# Power.net
KiCad netlist of a schematic drawn in Altium Designer
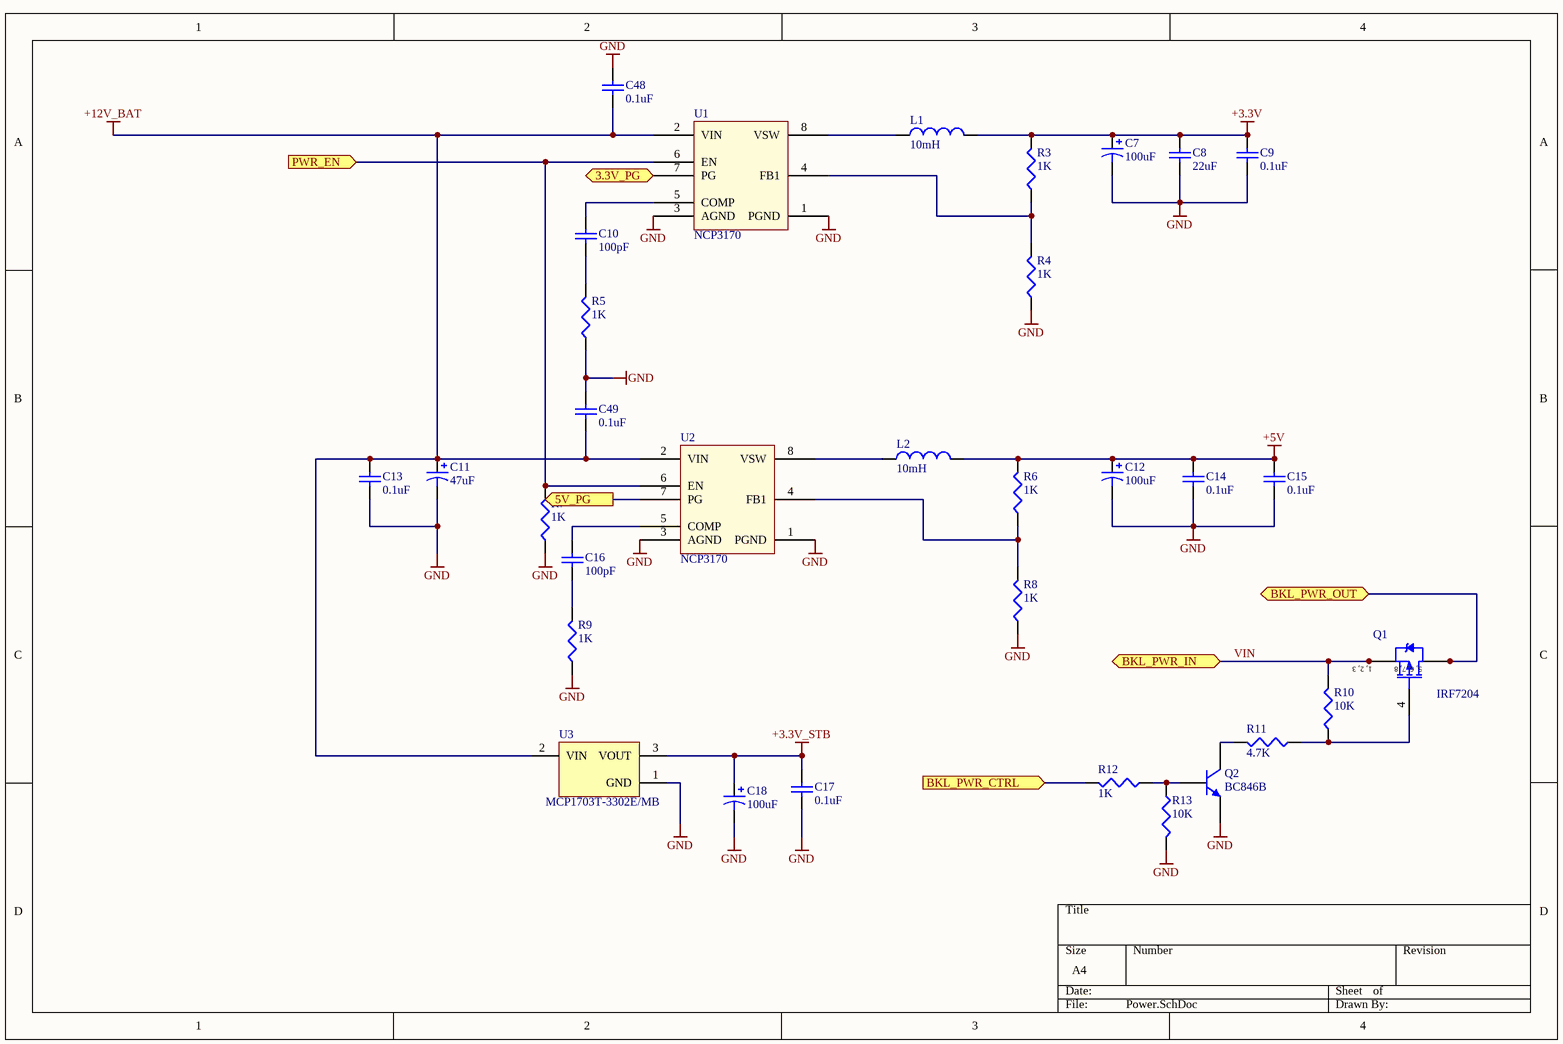
[diagram p0: Power.SchDoc]

(export (version "E")
  (design (tool "Eeschema 10.0.6"))
  (components
    (comp (ref "C7")
      (value "100uF")
      (footprint "6032")
      (fields (field (name "PUBLISHER") "Altium Limited"))
      (libsource (lib "Vishay Sprague Tantalum Chip Capacitor") (part "893D225X0025C2"))
    )
    (comp (ref "C8")
      (value "22uF")
      (footprint "2012[0805]")
      (description "Ceramic Chip Capacitor - Standard")
      (fields (field (name "PUBLISHER") "Altium Limited"))
      (libsource (lib "ResAndCaps") (part "C0805"))
    )
    (comp (ref "C9")
      (value "0.1uF")
      (footprint "2012[0805]")
      (description "Ceramic Chip Capacitor - Standard")
      (fields (field (name "PUBLISHER") "Altium Limited"))
      (libsource (lib "ResAndCaps") (part "C0805"))
    )
    (comp (ref "C10")
      (value "100pF")
      (footprint "1608[0603]")
      (description "Ceramic Chip Capacitor - Standard")
      (fields (field (name "PUBLISHER") "Altium Limited"))
      (libsource (lib "ResAndCaps") (part "C0603"))
    )
    (comp (ref "C11")
      (value "47uF")
      (footprint "7343")
      (fields (field (name "PUBLISHER") "Altium Limited"))
      (libsource (lib "Vishay Sprague Tantalum Chip Capacitor") (part "893D156X0025D2"))
    )
    (comp (ref "C12")
      (value "100uF")
      (footprint "6032")
      (fields (field (name "PUBLISHER") "Altium Limited"))
      (libsource (lib "Vishay Sprague Tantalum Chip Capacitor") (part "893D225X0025C2"))
    )
    (comp (ref "C13")
      (value "0.1uF")
      (footprint "2012[0805]")
      (description "Ceramic Chip Capacitor - Standard")
      (fields (field (name "PUBLISHER") "Altium Limited"))
      (libsource (lib "ResAndCaps") (part "C0805"))
    )
    (comp (ref "C14")
      (value "0.1uF")
      (footprint "2012[0805]")
      (description "Ceramic Chip Capacitor - Standard")
      (fields (field (name "PUBLISHER") "Altium Limited"))
      (libsource (lib "ResAndCaps") (part "C0805"))
    )
    (comp (ref "C15")
      (value "0.1uF")
      (footprint "2012[0805]")
      (description "Ceramic Chip Capacitor - Standard")
      (fields (field (name "PUBLISHER") "Altium Limited"))
      (libsource (lib "ResAndCaps") (part "C0805"))
    )
    (comp (ref "C16")
      (value "100pF")
      (footprint "1608[0603]")
      (description "Ceramic Chip Capacitor - Standard")
      (fields (field (name "PUBLISHER") "Altium Limited"))
      (libsource (lib "ResAndCaps") (part "C0603"))
    )
    (comp (ref "C17")
      (value "0.1uF")
      (footprint "2012[0805]")
      (description "Ceramic Chip Capacitor - Standard")
      (fields (field (name "PUBLISHER") "Altium Limited"))
      (libsource (lib "ResAndCaps") (part "C0805"))
    )
    (comp (ref "C18")
      (value "100uF")
      (footprint "6032")
      (fields (field (name "PUBLISHER") "Altium Limited"))
      (libsource (lib "Vishay Sprague Tantalum Chip Capacitor") (part "893D225X0025C2"))
    )
    (comp (ref "C48")
      (value "0.1uF")
      (footprint "2012[0805]")
      (description "Ceramic Chip Capacitor - Standard")
      (fields (field (name "PUBLISHER") "Altium Limited"))
      (libsource (lib "ResAndCaps") (part "C0805"))
    )
    (comp (ref "C49")
      (value "0.1uF")
      (footprint "2012[0805]")
      (description "Ceramic Chip Capacitor - Standard")
      (fields (field (name "PUBLISHER") "Altium Limited"))
      (libsource (lib "ResAndCaps") (part "C0805"))
    )
    (comp (ref "L1")
      (value "10mH")
      (footprint "CDRH127")
      (description "Inductor")
      (fields (field (name "PUBLISHER") "Altium Limited"))
      (libsource (lib "inductors") (part "Inductor"))
    )
    (comp (ref "L2")
      (value "10mH")
      (footprint "CDRH127")
      (description "Inductor")
      (fields (field (name "PUBLISHER") "Altium Limited"))
      (libsource (lib "inductors") (part "Inductor"))
    )
    (comp (ref "Q1")
      (value "IRF7204")
      (footprint "SO-8_N")
      (description "HEXFET Power MOSFET")
      (fields (field (name "PUBLISHER") "Altium Limited"))
      (libsource (lib "IR Discrete MOSFET - Power") (part "IRF7204"))
    )
    (comp (ref "Q2")
      (value "BC846B")
      (footprint "SOT23_N")
      (description "NPN General-purpose Transistor")
      (fields (field (name "PUBLISHER") "Altium Limited"))
      (libsource (lib "Philips Discrete BJT - Low Power") (part "BC846B"))
    )
    (comp (ref "R3")
      (value "1K")
      (footprint "R2012[0805]")
      (description "R0805")
      (fields (field (name "PUBLISHER") "Altium Limited"))
      (libsource (lib "ResAndCaps") (part "R0805"))
    )
    (comp (ref "R4")
      (value "1K")
      (footprint "R2012[0805]")
      (description "R0805")
      (fields (field (name "PUBLISHER") "Altium Limited"))
      (libsource (lib "ResAndCaps") (part "R0805"))
    )
    (comp (ref "R5")
      (value "1K")
      (footprint "footprints:R1608[0603]")
      (description "R0603")
      (fields (field (name "PUBLISHER") "Altium Limited"))
      (libsource (lib "ResAndCaps") (part "R0603"))
    )
    (comp (ref "R6")
      (value "1K")
      (footprint "R2012[0805]")
      (description "R0805")
      (fields (field (name "PUBLISHER") "Altium Limited"))
      (libsource (lib "ResAndCaps") (part "R0805"))
    )
    (comp (ref "R7")
      (value "1K")
      (footprint "footprints:R1608[0603]")
      (description "R0603")
      (fields (field (name "PUBLISHER") "Altium Limited"))
      (libsource (lib "ResAndCaps") (part "R0603"))
    )
    (comp (ref "R8")
      (value "1K")
      (footprint "R2012[0805]")
      (description "R0805")
      (fields (field (name "PUBLISHER") "Altium Limited"))
      (libsource (lib "ResAndCaps") (part "R0805"))
    )
    (comp (ref "R9")
      (value "1K")
      (footprint "footprints:R1608[0603]")
      (description "R0603")
      (fields (field (name "PUBLISHER") "Altium Limited"))
      (libsource (lib "ResAndCaps") (part "R0603"))
    )
    (comp (ref "R10")
      (value "10K")
      (footprint "R2012[0805]")
      (description "R0805")
      (fields (field (name "PUBLISHER") "Altium Limited"))
      (libsource (lib "ResAndCaps") (part "R0805"))
    )
    (comp (ref "R11")
      (value "4.7K")
      (footprint "R2012[0805]")
      (description "R0805")
      (fields (field (name "PUBLISHER") "Altium Limited"))
      (libsource (lib "ResAndCaps") (part "R0805"))
    )
    (comp (ref "R12")
      (value "1K")
      (footprint "R2012[0805]")
      (description "R0805")
      (fields (field (name "PUBLISHER") "Altium Limited"))
      (libsource (lib "ResAndCaps") (part "R0805"))
    )
    (comp (ref "R13")
      (value "10K")
      (footprint "R2012[0805]")
      (description "R0805")
      (fields (field (name "PUBLISHER") "Altium Limited"))
      (libsource (lib "ResAndCaps") (part "R0805"))
    )
    (comp (ref "U1")
      (value "NCP3170")
      (footprint "SOIC127P600-8AM")
      (libsource (lib "on semi") (part "TCP3170"))
    )
    (comp (ref "U2")
      (value "NCP3170")
      (footprint "SOIC127P600-8AM")
      (libsource (lib "on semi") (part "TCP3170"))
    )
    (comp (ref "U3")
      (value "MCP1703T-3302E/MB")
      (footprint "SOT-89-MB3_N")
      (libsource (lib "Microchip Power Management Line Regulator") (part "MCP1703T-3302E/MB"))
    )
  )
  (nets
    (net (code "1") (name "+3.3V") (class "Default")
      (node (ref "C7") (pin "1") (pinfunction "1_1") (pintype "passive"))
      (node (ref "C8") (pin "2") (pinfunction "2_2") (pintype "passive"))
      (node (ref "C9") (pin "2") (pinfunction "2_2") (pintype "passive"))
      (node (ref "L1") (pin "2") (pinfunction "2_2") (pintype "passive"))
      (node (ref "R3") (pin "2") (pinfunction "2_2") (pintype "passive"))
    )
    (net (code "2") (name "+3.3V_STB") (class "Default")
      (node (ref "C17") (pin "2") (pinfunction "2_2") (pintype "passive"))
      (node (ref "C18") (pin "1") (pinfunction "1_1") (pintype "passive"))
      (node (ref "U3") (pin "3") (pinfunction "VOUT_3") (pintype "power_in"))
    )
    (net (code "3") (name "+5V") (class "Default")
      (node (ref "C12") (pin "1") (pinfunction "1_1") (pintype "passive"))
      (node (ref "C14") (pin "2") (pinfunction "2_2") (pintype "passive"))
      (node (ref "C15") (pin "2") (pinfunction "2_2") (pintype "passive"))
      (node (ref "L2") (pin "2") (pinfunction "2_2") (pintype "passive"))
      (node (ref "R6") (pin "2") (pinfunction "2_2") (pintype "passive"))
    )
    (net (code "4") (name "+12V_BAT") (class "Default")
      (node (ref "C11") (pin "1") (pinfunction "1_1") (pintype "passive"))
      (node (ref "C13") (pin "2") (pinfunction "2_2") (pintype "passive"))
      (node (ref "C48") (pin "1") (pinfunction "1_1") (pintype "passive"))
      (node (ref "C49") (pin "1") (pinfunction "1_1") (pintype "passive"))
      (node (ref "U1") (pin "2") (pinfunction "VIN_2") (pintype "passive"))
      (node (ref "U2") (pin "2") (pinfunction "VIN_2") (pintype "passive"))
      (node (ref "U3") (pin "2") (pinfunction "VIN_2") (pintype "power_in"))
    )
    (net (code "5") (name "/3.3V_PG") (class "Default")
      (node (ref "U1") (pin "7") (pinfunction "PG_7") (pintype "passive"))
    )
    (net (code "6") (name "/5V_PG") (class "Default")
      (node (ref "U2") (pin "7") (pinfunction "PG_7") (pintype "passive"))
    )
    (net (code "7") (name "/BKL_PWR_CTRL") (class "Default")
      (node (ref "R12") (pin "2") (pinfunction "2_2") (pintype "passive"))
    )
    (net (code "8") (name "/BKL_PWR_OUT") (class "Default")
      (node (ref "Q1") (pin "5") (pinfunction "D_5") (pintype "passive"))
      (node (ref "Q1") (pin "6") (pinfunction "D_6") (pintype "passive"))
      (node (ref "Q1") (pin "7") (pinfunction "D_7") (pintype "passive"))
      (node (ref "Q1") (pin "8") (pinfunction "D_8") (pintype "passive"))
    )
    (net (code "9") (name "/PWR_EN") (class "Default")
      (node (ref "R7") (pin "2") (pinfunction "2_2") (pintype "passive"))
      (node (ref "U1") (pin "6") (pinfunction "EN_6") (pintype "passive"))
      (node (ref "U2") (pin "6") (pinfunction "EN_6") (pintype "passive"))
    )
    (net (code "10") (name "/VIN") (class "Default")
      (node (ref "Q1") (pin "1") (pinfunction "S_1") (pintype "passive"))
      (node (ref "Q1") (pin "2") (pinfunction "S_2") (pintype "passive"))
      (node (ref "Q1") (pin "3") (pinfunction "S_3") (pintype "passive"))
      (node (ref "R10") (pin "2") (pinfunction "2_2") (pintype "passive"))
    )
    (net (code "11") (name "GND") (class "Default")
      (node (ref "C11") (pin "2") (pinfunction "2_2") (pintype "passive"))
      (node (ref "C12") (pin "2") (pinfunction "2_2") (pintype "passive"))
      (node (ref "C13") (pin "1") (pinfunction "1_1") (pintype "passive"))
      (node (ref "C14") (pin "1") (pinfunction "1_1") (pintype "passive"))
      (node (ref "C15") (pin "1") (pinfunction "1_1") (pintype "passive"))
      (node (ref "C17") (pin "1") (pinfunction "1_1") (pintype "passive"))
      (node (ref "C18") (pin "2") (pinfunction "2_2") (pintype "passive"))
      (node (ref "C48") (pin "2") (pinfunction "2_2") (pintype "passive"))
      (node (ref "C49") (pin "2") (pinfunction "2_2") (pintype "passive"))
      (node (ref "C7") (pin "2") (pinfunction "2_2") (pintype "passive"))
      (node (ref "C8") (pin "1") (pinfunction "1_1") (pintype "passive"))
      (node (ref "C9") (pin "1") (pinfunction "1_1") (pintype "passive"))
      (node (ref "Q2") (pin "2") (pinfunction "E_2") (pintype "passive"))
      (node (ref "R13") (pin "2") (pinfunction "2_2") (pintype "passive"))
      (node (ref "R4") (pin "1") (pinfunction "1_1") (pintype "passive"))
      (node (ref "R5") (pin "1") (pinfunction "1_1") (pintype "passive"))
      (node (ref "R7") (pin "1") (pinfunction "1_1") (pintype "passive"))
      (node (ref "R8") (pin "1") (pinfunction "1_1") (pintype "passive"))
      (node (ref "R9") (pin "1") (pinfunction "1_1") (pintype "passive"))
      (node (ref "U1") (pin "1") (pinfunction "PGND_1") (pintype "passive"))
      (node (ref "U1") (pin "3") (pinfunction "AGND_3") (pintype "passive"))
      (node (ref "U2") (pin "1") (pinfunction "PGND_1") (pintype "passive"))
      (node (ref "U2") (pin "3") (pinfunction "AGND_3") (pintype "passive"))
      (node (ref "U3") (pin "1") (pinfunction "GND_1") (pintype "power_in"))
    )
    (net (code "12") (name "Net-(C10-Pad1)") (class "Default")
      (node (ref "C10") (pin "1") (pinfunction "1_1") (pintype "passive"))
      (node (ref "R5") (pin "2") (pinfunction "2_2") (pintype "passive"))
    )
    (net (code "13") (name "Net-(C16-Pad1)") (class "Default")
      (node (ref "C16") (pin "1") (pinfunction "1_1") (pintype "passive"))
      (node (ref "R9") (pin "2") (pinfunction "2_2") (pintype "passive"))
    )
    (net (code "14") (name "Net-(Q1-G)") (class "Default")
      (node (ref "Q1") (pin "4") (pinfunction "G_4") (pintype "passive"))
      (node (ref "R10") (pin "1") (pinfunction "1_1") (pintype "passive"))
      (node (ref "R11") (pin "1") (pinfunction "1_1") (pintype "passive"))
    )
    (net (code "15") (name "Net-(Q2-B)") (class "Default")
      (node (ref "Q2") (pin "1") (pinfunction "B_1") (pintype "passive"))
      (node (ref "R12") (pin "1") (pinfunction "1_1") (pintype "passive"))
      (node (ref "R13") (pin "1") (pinfunction "1_1") (pintype "passive"))
    )
    (net (code "16") (name "Net-(Q2-C)") (class "Default")
      (node (ref "Q2") (pin "3") (pinfunction "C_3") (pintype "passive"))
      (node (ref "R11") (pin "2") (pinfunction "2_2") (pintype "passive"))
    )
    (net (code "17") (name "Net-(U1-COMP)") (class "Default")
      (node (ref "C10") (pin "2") (pinfunction "2_2") (pintype "passive"))
      (node (ref "U1") (pin "5") (pinfunction "COMP_5") (pintype "passive"))
    )
    (net (code "18") (name "Net-(U1-FB1)") (class "Default")
      (node (ref "R3") (pin "1") (pinfunction "1_1") (pintype "passive"))
      (node (ref "R4") (pin "2") (pinfunction "2_2") (pintype "passive"))
      (node (ref "U1") (pin "4") (pinfunction "FB1_4") (pintype "passive"))
    )
    (net (code "19") (name "Net-(U1-VSW)") (class "Default")
      (node (ref "L1") (pin "1") (pinfunction "1_1") (pintype "passive"))
      (node (ref "U1") (pin "8") (pinfunction "VSW_8") (pintype "passive"))
    )
    (net (code "20") (name "Net-(U2-COMP)") (class "Default")
      (node (ref "C16") (pin "2") (pinfunction "2_2") (pintype "passive"))
      (node (ref "U2") (pin "5") (pinfunction "COMP_5") (pintype "passive"))
    )
    (net (code "21") (name "Net-(U2-FB1)") (class "Default")
      (node (ref "R6") (pin "1") (pinfunction "1_1") (pintype "passive"))
      (node (ref "R8") (pin "2") (pinfunction "2_2") (pintype "passive"))
      (node (ref "U2") (pin "4") (pinfunction "FB1_4") (pintype "passive"))
    )
    (net (code "22") (name "Net-(U2-VSW)") (class "Default")
      (node (ref "L2") (pin "1") (pinfunction "1_1") (pintype "passive"))
      (node (ref "U2") (pin "8") (pinfunction "VSW_8") (pintype "passive"))
    )
  )
)
